# RZ120.net
KiCad netlist of a schematic drawn in Altium Designer
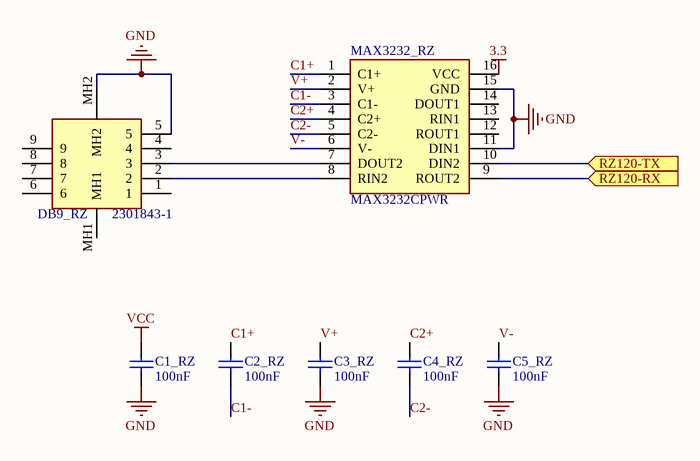
[diagram p0: RZ120.SchDoc]

(export (version "E")
  (design (tool "Eeschema 10.0.6"))
  (components
    (comp (ref "C1_RZ")
      (value "100nF")
      (footprint "1608[0603]")
      (description "Capacitor (Semiconductor SIM Model)")
      (fields (field (name "Comment") "Cap Semi") (field (name "PUBLISHER") "Altium Limited"))
      (libsource (lib "Miscellaneous Devices") (part "Cap Semi"))
    )
    (comp (ref "C2_RZ")
      (value "100nF")
      (footprint "1608[0603]")
      (description "Capacitor (Semiconductor SIM Model)")
      (fields (field (name "Comment") "Cap Semi") (field (name "PUBLISHER") "Altium Limited"))
      (libsource (lib "Miscellaneous Devices") (part "Cap Semi"))
    )
    (comp (ref "C3_RZ")
      (value "100nF")
      (footprint "1608[0603]")
      (description "Capacitor (Semiconductor SIM Model)")
      (fields (field (name "Comment") "Cap Semi") (field (name "PUBLISHER") "Altium Limited"))
      (libsource (lib "Miscellaneous Devices") (part "Cap Semi"))
    )
    (comp (ref "C4_RZ")
      (value "100nF")
      (footprint "1608[0603]")
      (description "Capacitor (Semiconductor SIM Model)")
      (fields (field (name "Comment") "Cap Semi") (field (name "PUBLISHER") "Altium Limited"))
      (libsource (lib "Miscellaneous Devices") (part "Cap Semi"))
    )
    (comp (ref "C5_RZ")
      (value "100nF")
      (footprint "1608[0603]")
      (description "Capacitor (Semiconductor SIM Model)")
      (fields (field (name "Comment") "Cap Semi") (field (name "PUBLISHER") "Altium Limited"))
      (libsource (lib "Miscellaneous Devices") (part "Cap Semi"))
    )
    (comp (ref "DB9_RZ")
      (value "2301843-1")
      (footprint "LX1-RS232:23018431")
      (description "Connector")
      (fields (field (name "MOUSER PART NUMBER") "571-2301843-1"))
      (libsource (lib "LX1-RS232") (part "2301843-1"))
    )
    (comp (ref "MAX3232_RZ")
      (value "MAX3232CPWR")
      (footprint "LX1-RS232:SOP65P640X120-16N")
      (description "Integrated Circuit")
      (fields (field (name "MOUSER PART NUMBER") "595-MAX3232CPWR"))
      (libsource (lib "LX1-RS232") (part "MAX3232CPWR"))
    )
  )
  (nets
    (net (code "1") (name "/C1+") (class "Default")
      (node (ref "C2_RZ") (pin "2") (pinfunction "2_2") (pintype "passive"))
      (node (ref "MAX3232_RZ") (pin "1") (pinfunction "C1+_1") (pintype "passive"))
    )
    (net (code "2") (name "/C1-") (class "Default")
      (node (ref "C2_RZ") (pin "1") (pinfunction "1_1") (pintype "passive"))
      (node (ref "MAX3232_RZ") (pin "3") (pinfunction "C1-_3") (pintype "passive"))
    )
    (net (code "3") (name "/C2+") (class "Default")
      (node (ref "C4_RZ") (pin "2") (pinfunction "2_2") (pintype "passive"))
      (node (ref "MAX3232_RZ") (pin "4") (pinfunction "C2+_4") (pintype "passive"))
    )
    (net (code "4") (name "/C2-") (class "Default")
      (node (ref "C4_RZ") (pin "1") (pinfunction "1_1") (pintype "passive"))
      (node (ref "MAX3232_RZ") (pin "5") (pinfunction "C2-_5") (pintype "passive"))
    )
    (net (code "5") (name "/RZ120-RX") (class "Default")
      (node (ref "MAX3232_RZ") (pin "9") (pinfunction "ROUT2_9") (pintype "passive"))
    )
    (net (code "6") (name "/RZ120-TX") (class "Default")
      (node (ref "MAX3232_RZ") (pin "10") (pinfunction "DIN2_10") (pintype "passive"))
    )
    (net (code "7") (name "/V+") (class "Default")
      (node (ref "C3_RZ") (pin "2") (pinfunction "2_2") (pintype "passive"))
      (node (ref "MAX3232_RZ") (pin "2") (pinfunction "V+_2") (pintype "passive"))
    )
    (net (code "8") (name "/V-") (class "Default")
      (node (ref "C5_RZ") (pin "2") (pinfunction "2_2") (pintype "passive"))
      (node (ref "MAX3232_RZ") (pin "6") (pinfunction "V-_6") (pintype "passive"))
    )
    (net (code "9") (name "3.3") (class "Default")
      (node (ref "MAX3232_RZ") (pin "16") (pinfunction "VCC_16") (pintype "passive"))
    )
    (net (code "10") (name "GND") (class "Default")
      (node (ref "C1_RZ") (pin "1") (pinfunction "1_1") (pintype "passive"))
      (node (ref "C3_RZ") (pin "1") (pinfunction "1_1") (pintype "passive"))
      (node (ref "C5_RZ") (pin "1") (pinfunction "1_1") (pintype "passive"))
      (node (ref "DB9_RZ") (pin "5") (pinfunction "5_5") (pintype "passive"))
      (node (ref "DB9_RZ") (pin "MH2") (pinfunction "MH2_MH2") (pintype "passive"))
      (node (ref "MAX3232_RZ") (pin "11") (pinfunction "DIN1_11") (pintype "passive"))
      (node (ref "MAX3232_RZ") (pin "15") (pinfunction "GND_15") (pintype "passive"))
    )
    (net (code "11") (name "Net-(MAX3232_RZ-DOUT2)") (class "Default")
      (node (ref "DB9_RZ") (pin "3") (pinfunction "3_3") (pintype "passive"))
      (node (ref "MAX3232_RZ") (pin "7") (pinfunction "DOUT2_7") (pintype "passive"))
    )
    (net (code "12") (name "Net-(MAX3232_RZ-RIN2)") (class "Default")
      (node (ref "DB9_RZ") (pin "2") (pinfunction "2_2") (pintype "passive"))
      (node (ref "MAX3232_RZ") (pin "8") (pinfunction "RIN2_8") (pintype "passive"))
    )
    (net (code "13") (name "VCC") (class "Default")
      (node (ref "C1_RZ") (pin "2") (pinfunction "2_2") (pintype "passive"))
    )
    (net (code "14") (name "unconnected-(DB9_RZ-Pad1)") (class "Default")
      (node (ref "DB9_RZ") (pin "1") (pinfunction "1_1") (pintype "passive"))
    )
    (net (code "15") (name "unconnected-(DB9_RZ-Pad4)") (class "Default")
      (node (ref "DB9_RZ") (pin "4") (pinfunction "4_4") (pintype "passive"))
    )
    (net (code "16") (name "unconnected-(DB9_RZ-Pad6)") (class "Default")
      (node (ref "DB9_RZ") (pin "6") (pinfunction "6_6") (pintype "passive"))
    )
    (net (code "17") (name "unconnected-(DB9_RZ-Pad7)") (class "Default")
      (node (ref "DB9_RZ") (pin "7") (pinfunction "7_7") (pintype "passive"))
    )
    (net (code "18") (name "unconnected-(DB9_RZ-Pad8)") (class "Default")
      (node (ref "DB9_RZ") (pin "8") (pinfunction "8_8") (pintype "passive"))
    )
    (net (code "19") (name "unconnected-(DB9_RZ-Pad9)") (class "Default")
      (node (ref "DB9_RZ") (pin "9") (pinfunction "9_9") (pintype "passive"))
    )
    (net (code "20") (name "unconnected-(DB9_RZ-PadMH1)") (class "Default")
      (node (ref "DB9_RZ") (pin "MH1") (pinfunction "MH1_MH1") (pintype "passive"))
    )
    (net (code "21") (name "unconnected-(MAX3232_RZ-DOUT1-Pad14)") (class "Default")
      (node (ref "MAX3232_RZ") (pin "14") (pinfunction "DOUT1_14") (pintype "passive"))
    )
    (net (code "22") (name "unconnected-(MAX3232_RZ-RIN1-Pad13)") (class "Default")
      (node (ref "MAX3232_RZ") (pin "13") (pinfunction "RIN1_13") (pintype "passive"))
    )
    (net (code "23") (name "unconnected-(MAX3232_RZ-ROUT1-Pad12)") (class "Default")
      (node (ref "MAX3232_RZ") (pin "12") (pinfunction "ROUT1_12") (pintype "passive"))
    )
  )
)
